# Main-Board.net
KiCad netlist of a schematic drawn in EAGLE
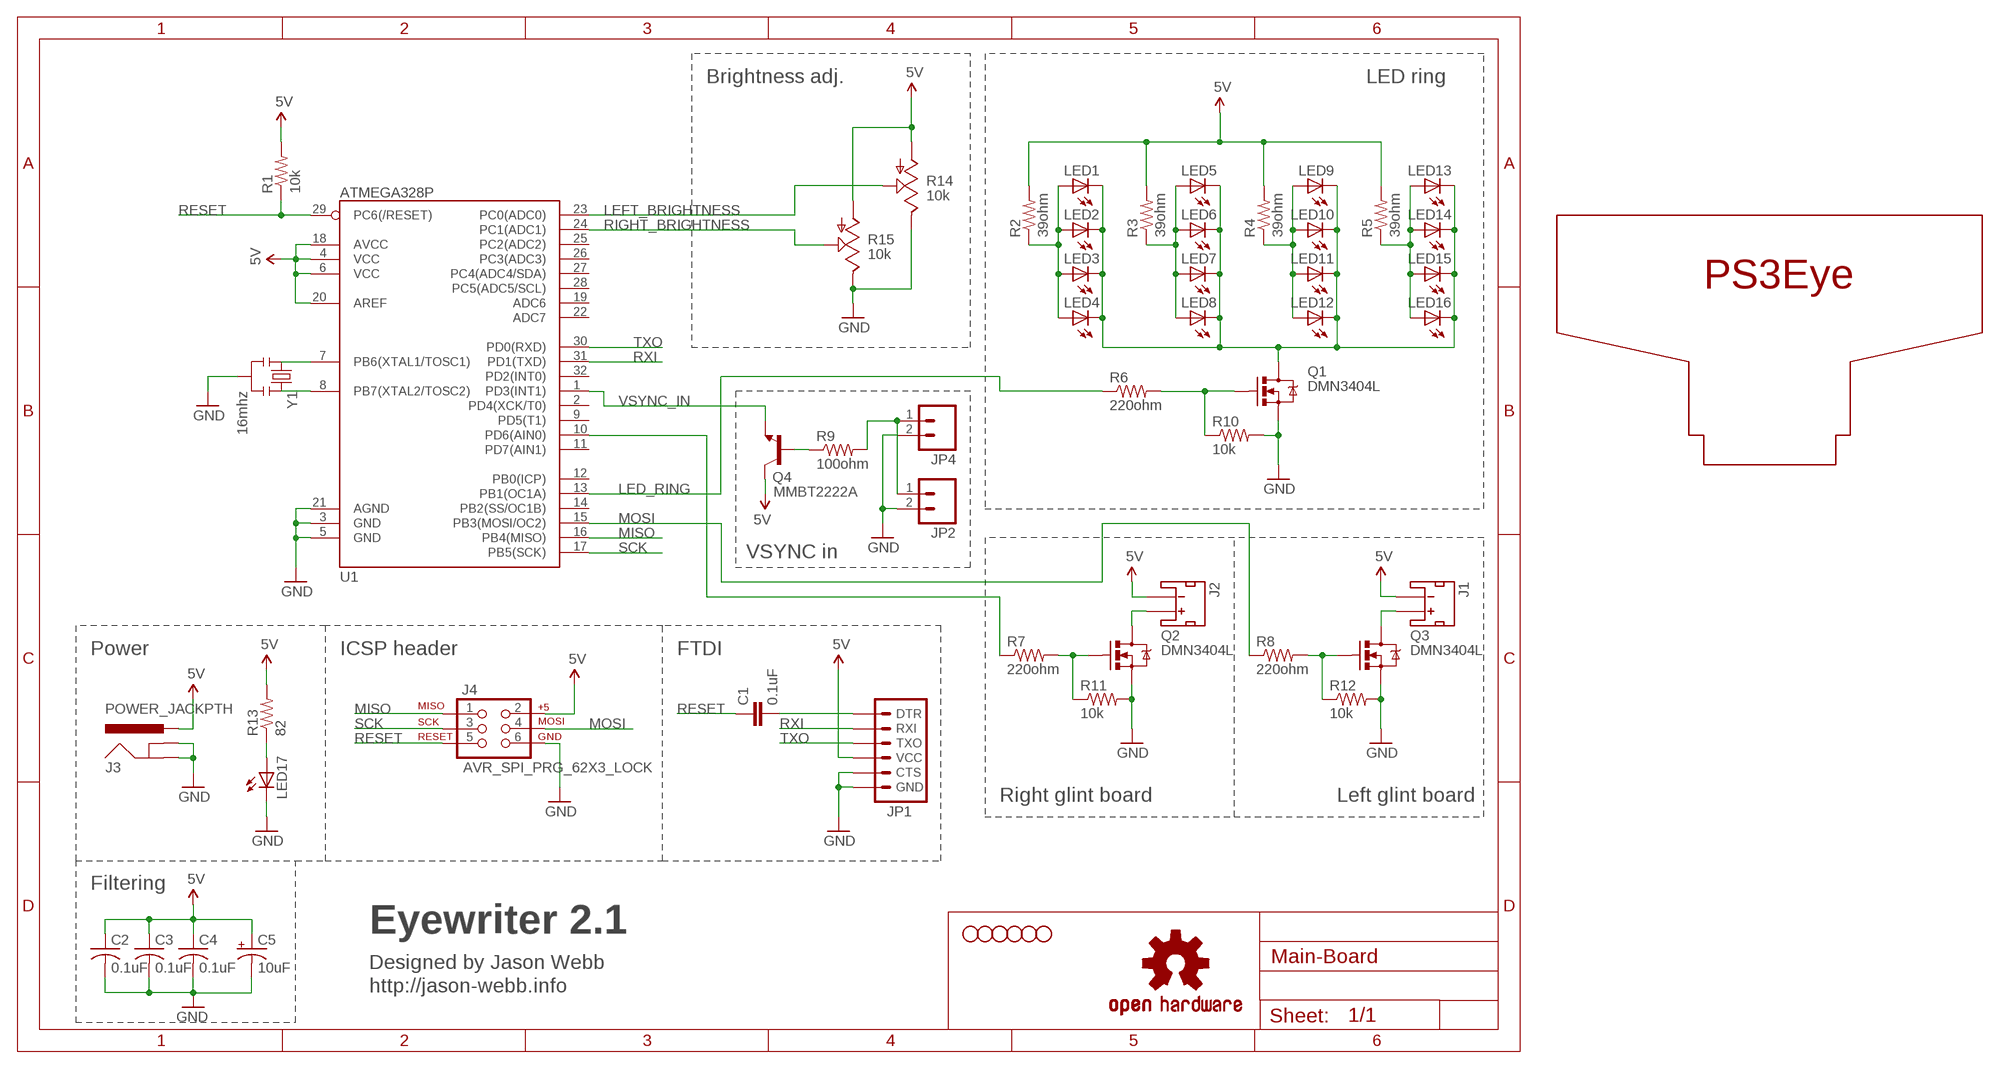
[diagram p0: schematic, sheet 1]

(export (version "E")
  (design (tool "Eeschema 10.0.6"))
  (components
    (comp (ref "C1")
      (value "0.1uF")
      (footprint "eagle-import:0805")
      (libsource (lib "eagle-import") (part "CAP0805"))
    )
    (comp (ref "C2")
      (value "0.1uF")
      (footprint "eagle-import:C0805K")
      (libsource (lib "eagle-import") (part "C-USC0805K"))
    )
    (comp (ref "C3")
      (value "0.1uF")
      (footprint "eagle-import:C0805K")
      (libsource (lib "eagle-import") (part "C-USC0805K"))
    )
    (comp (ref "C4")
      (value "0.1uF")
      (footprint "eagle-import:C0805K")
      (libsource (lib "eagle-import") (part "C-USC0805K"))
    )
    (comp (ref "C5")
      (value "10uF")
      (footprint "eagle-import:A_3216-18R")
      (libsource (lib "eagle-import") (part "CPOL-USA/3216-18R"))
    )
    (comp (ref "J1")
      (value "JST_2MM_MALE")
      (footprint "eagle-import:JST-2-SMD")
      (libsource (lib "eagle-import") (part "JST_2MM_MALE"))
    )
    (comp (ref "J2")
      (value "JST_2MM_MALE")
      (footprint "eagle-import:JST-2-SMD")
      (libsource (lib "eagle-import") (part "JST_2MM_MALE"))
    )
    (comp (ref "J3")
      (value "POWER_JACKPTH")
      (footprint "eagle-import:POWER_JACK_PTH")
      (libsource (lib "eagle-import") (part "POWER_JACKPTH"))
    )
    (comp (ref "J4")
      (value "AVR_SPI_PRG_62X3_LOCK")
      (footprint "eagle-import:2X3_LOCK")
      (libsource (lib "eagle-import") (part "AVR_SPI_PRG_62X3_LOCK"))
    )
    (comp (ref "JP1")
      (value "ARDUINO_SERIAL_PROGRAMLOCK")
      (footprint "eagle-import:1X06_LOCK")
      (libsource (lib "eagle-import") (part "ARDUINO_SERIAL_PROGRAMLOCK"))
    )
    (comp (ref "JP2")
      (value "M02PTH")
      (footprint "eagle-import:1X02")
      (libsource (lib "eagle-import") (part "M02PTH"))
    )
    (comp (ref "JP4")
      (value "M02PTH")
      (footprint "eagle-import:1X02")
      (libsource (lib "eagle-import") (part "M02PTH"))
    )
    (comp (ref "LED1")
      (value "LED5MM")
      (footprint "eagle-import:LED5MM")
      (libsource (lib "eagle-import") (part "LED5MM"))
    )
    (comp (ref "LED2")
      (value "LED5MM")
      (footprint "eagle-import:LED5MM")
      (libsource (lib "eagle-import") (part "LED5MM"))
    )
    (comp (ref "LED3")
      (value "LED5MM")
      (footprint "eagle-import:LED5MM")
      (libsource (lib "eagle-import") (part "LED5MM"))
    )
    (comp (ref "LED4")
      (value "LED5MM")
      (footprint "eagle-import:LED5MM")
      (libsource (lib "eagle-import") (part "LED5MM"))
    )
    (comp (ref "LED5")
      (value "LED5MM")
      (footprint "eagle-import:LED5MM")
      (libsource (lib "eagle-import") (part "LED5MM"))
    )
    (comp (ref "LED6")
      (value "LED5MM")
      (footprint "eagle-import:LED5MM")
      (libsource (lib "eagle-import") (part "LED5MM"))
    )
    (comp (ref "LED7")
      (value "LED5MM")
      (footprint "eagle-import:LED5MM")
      (libsource (lib "eagle-import") (part "LED5MM"))
    )
    (comp (ref "LED8")
      (value "LED5MM")
      (footprint "eagle-import:LED5MM")
      (libsource (lib "eagle-import") (part "LED5MM"))
    )
    (comp (ref "LED9")
      (value "LED5MM")
      (footprint "eagle-import:LED5MM")
      (libsource (lib "eagle-import") (part "LED5MM"))
    )
    (comp (ref "LED10")
      (value "LED5MM")
      (footprint "eagle-import:LED5MM")
      (libsource (lib "eagle-import") (part "LED5MM"))
    )
    (comp (ref "LED11")
      (value "LED5MM")
      (footprint "eagle-import:LED5MM")
      (libsource (lib "eagle-import") (part "LED5MM"))
    )
    (comp (ref "LED12")
      (value "LED5MM")
      (footprint "eagle-import:LED5MM")
      (libsource (lib "eagle-import") (part "LED5MM"))
    )
    (comp (ref "LED13")
      (value "LED5MM")
      (footprint "eagle-import:LED5MM")
      (libsource (lib "eagle-import") (part "LED5MM"))
    )
    (comp (ref "LED14")
      (value "LED5MM")
      (footprint "eagle-import:LED5MM")
      (libsource (lib "eagle-import") (part "LED5MM"))
    )
    (comp (ref "LED15")
      (value "LED5MM")
      (footprint "eagle-import:LED5MM")
      (libsource (lib "eagle-import") (part "LED5MM"))
    )
    (comp (ref "LED16")
      (value "LED5MM")
      (footprint "eagle-import:LED5MM")
      (libsource (lib "eagle-import") (part "LED5MM"))
    )
    (comp (ref "LED17")
      (value "LEDCHIPLED_0805")
      (footprint "eagle-import:CHIPLED_0805")
      (libsource (lib "eagle-import") (part "LEDCHIPLED_0805"))
    )
    (comp (ref "LOGO1")
      (value "OSHW-LOGOL")
      (footprint "eagle-import:OSHW-LOGO-L")
      (libsource (lib "eagle-import") (part "OSHW-LOGOL"))
    )
    (comp (ref "Q1")
      (value "DMN3404L")
      (footprint "eagle-import:SOT23-3")
      (libsource (lib "eagle-import") (part "MOSFET-NCHANNELSMD"))
    )
    (comp (ref "Q2")
      (value "DMN3404L")
      (footprint "eagle-import:SOT23-3")
      (libsource (lib "eagle-import") (part "MOSFET-NCHANNELSMD"))
    )
    (comp (ref "Q3")
      (value "DMN3404L")
      (footprint "eagle-import:SOT23-3")
      (libsource (lib "eagle-import") (part "MOSFET-NCHANNELSMD"))
    )
    (comp (ref "Q4")
      (value "MMBT2222A")
      (footprint "eagle-import:SOT23")
      (libsource (lib "eagle-import") (part "TRANSISTOR_NPNSOT23"))
    )
    (comp (ref "R1")
      (value "10k")
      (footprint "eagle-import:0805")
      (libsource (lib "eagle-import") (part "RESISTOR0805-RES"))
    )
    (comp (ref "R2")
      (value "39ohm")
      (footprint "eagle-import:0309_10")
      (libsource (lib "eagle-import") (part "R-US_0309/10"))
    )
    (comp (ref "R3")
      (value "39ohm")
      (footprint "eagle-import:0309_10")
      (libsource (lib "eagle-import") (part "R-US_0309/10"))
    )
    (comp (ref "R4")
      (value "39ohm")
      (footprint "eagle-import:0309_10")
      (libsource (lib "eagle-import") (part "R-US_0309/10"))
    )
    (comp (ref "R5")
      (value "39ohm")
      (footprint "eagle-import:0309_10")
      (libsource (lib "eagle-import") (part "R-US_0309/10"))
    )
    (comp (ref "R6")
      (value "220ohm")
      (footprint "eagle-import:0805")
      (libsource (lib "eagle-import") (part "RESISTOR0805-RES"))
    )
    (comp (ref "R7")
      (value "220ohm")
      (footprint "eagle-import:0805")
      (libsource (lib "eagle-import") (part "RESISTOR0805-RES"))
    )
    (comp (ref "R8")
      (value "220ohm")
      (footprint "eagle-import:0805")
      (libsource (lib "eagle-import") (part "RESISTOR0805-RES"))
    )
    (comp (ref "R9")
      (value "100ohm")
      (footprint "eagle-import:0805")
      (libsource (lib "eagle-import") (part "RESISTOR0805-RES"))
    )
    (comp (ref "R10")
      (value "10k")
      (footprint "eagle-import:0805")
      (libsource (lib "eagle-import") (part "RESISTOR0805-RES"))
    )
    (comp (ref "R11")
      (value "10k")
      (footprint "eagle-import:0805")
      (libsource (lib "eagle-import") (part "RESISTOR0805-RES"))
    )
    (comp (ref "R12")
      (value "10k")
      (footprint "eagle-import:0805")
      (libsource (lib "eagle-import") (part "RESISTOR0805-RES"))
    )
    (comp (ref "R13")
      (value "82")
      (footprint "eagle-import:0805")
      (libsource (lib "eagle-import") (part "RESISTOR0805-RES"))
    )
    (comp (ref "R14")
      (value "10k")
      (footprint "eagle-import:ALPS_POT")
      (libsource (lib "eagle-import") (part "POT"))
    )
    (comp (ref "R15")
      (value "10k")
      (footprint "eagle-import:ALPS_POT")
      (libsource (lib "eagle-import") (part "POT"))
    )
    (comp (ref "STANDOFF1")
      (value "STAND-OFF")
      (footprint "eagle-import:STAND-OFF")
      (libsource (lib "eagle-import") (part "STAND-OFF"))
    )
    (comp (ref "STANDOFF2")
      (value "STAND-OFF")
      (footprint "eagle-import:STAND-OFF")
      (libsource (lib "eagle-import") (part "STAND-OFF"))
    )
    (comp (ref "STANDOFF3")
      (value "STAND-OFF")
      (footprint "eagle-import:STAND-OFF")
      (libsource (lib "eagle-import") (part "STAND-OFF"))
    )
    (comp (ref "STANDOFF4")
      (value "STAND-OFF")
      (footprint "eagle-import:STAND-OFF")
      (libsource (lib "eagle-import") (part "STAND-OFF"))
    )
    (comp (ref "STANDOFF5")
      (value "STAND-OFF")
      (footprint "eagle-import:STAND-OFF")
      (libsource (lib "eagle-import") (part "STAND-OFF"))
    )
    (comp (ref "STANDOFF6")
      (value "STAND-OFF")
      (footprint "eagle-import:STAND-OFF")
      (libsource (lib "eagle-import") (part "STAND-OFF"))
    )
    (comp (ref "U$1")
      (value "PS3EYE")
      (footprint "eagle-import:PS3EYE")
      (libsource (lib "eagle-import") (part "PS3EYE"))
    )
    (comp (ref "U1")
      (value "ATMEGA328P")
      (footprint "eagle-import:TQFP32-08")
      (libsource (lib "eagle-import") (part "ATMEGA328_SMT"))
    )
    (comp (ref "Y1")
      (value "16mhz")
      (footprint "eagle-import:RESONATOR-SMD")
      (libsource (lib "eagle-import") (part "RESONATOR16MHZ"))
    )
  )
  (nets
    (net (code "1") (name "/LED_RING") (class "Default")
      (node (ref "R6") (pin "1") (pinfunction "1_1") (pintype "passive"))
      (node (ref "U1") (pin "13") (pinfunction "PB1(OC1A)_13") (pintype "bidirectional"))
    )
    (net (code "2") (name "/LEFT_BRIGHTNESS") (class "Default")
      (node (ref "R14") (pin "P$2") (pinfunction "S_P$2") (pintype "passive"))
      (node (ref "U1") (pin "23") (pinfunction "PC0(ADC0)_23") (pintype "bidirectional"))
    )
    (net (code "3") (name "/MISO") (class "Default")
      (node (ref "J4") (pin "1") (pinfunction "1_1") (pintype "passive"))
      (node (ref "U1") (pin "16") (pinfunction "PB4(MISO)_16") (pintype "bidirectional"))
    )
    (net (code "4") (name "/MOSI") (class "Default")
      (node (ref "J4") (pin "4") (pinfunction "4_4") (pintype "passive"))
      (node (ref "R7") (pin "1") (pinfunction "1_1") (pintype "passive"))
      (node (ref "U1") (pin "10") (pinfunction "PD6(AIN0)_10") (pintype "bidirectional"))
    )
    (net (code "5") (name "/RESET") (class "Default")
      (node (ref "C1") (pin "1") (pinfunction "1_1") (pintype "passive"))
      (node (ref "J4") (pin "5") (pinfunction "5_5") (pintype "passive"))
      (node (ref "R1") (pin "1") (pinfunction "1_1") (pintype "passive"))
      (node (ref "U1") (pin "29") (pinfunction "PC6(/RESET)_29") (pintype "bidirectional"))
    )
    (net (code "6") (name "/RIGHT_BRIGHTNESS") (class "Default")
      (node (ref "R15") (pin "P$2") (pinfunction "S_P$2") (pintype "passive"))
      (node (ref "U1") (pin "24") (pinfunction "PC1(ADC1)_24") (pintype "bidirectional"))
    )
    (net (code "7") (name "/RXI") (class "Default")
      (node (ref "JP1") (pin "2") (pinfunction "RXI_2") (pintype "passive"))
      (node (ref "U1") (pin "31") (pinfunction "PD1(TXD)_31") (pintype "bidirectional"))
    )
    (net (code "8") (name "/SCK") (class "Default")
      (node (ref "J4") (pin "3") (pinfunction "3_3") (pintype "passive"))
      (node (ref "U1") (pin "17") (pinfunction "PB5(SCK)_17") (pintype "bidirectional"))
    )
    (net (code "9") (name "/TXO") (class "Default")
      (node (ref "JP1") (pin "3") (pinfunction "TXO_3") (pintype "passive"))
      (node (ref "U1") (pin "30") (pinfunction "PD0(RXD)_30") (pintype "bidirectional"))
    )
    (net (code "10") (name "/VSYNC_IN") (class "Default")
      (node (ref "Q4") (pin "2") (pinfunction "E_2") (pintype "passive"))
      (node (ref "U1") (pin "1") (pinfunction "PD3(INT1)_1") (pintype "bidirectional"))
    )
    (net (code "11") (name "5V") (class "Default")
      (node (ref "C2") (pin "1") (pinfunction "1_1") (pintype "passive"))
      (node (ref "C3") (pin "1") (pinfunction "1_1") (pintype "passive"))
      (node (ref "C4") (pin "1") (pinfunction "1_1") (pintype "passive"))
      (node (ref "C5") (pin "+") (pinfunction "+_+") (pintype "passive"))
      (node (ref "J1") (pin "1") (pinfunction "-_1") (pintype "bidirectional"))
      (node (ref "J2") (pin "1") (pinfunction "-_1") (pintype "bidirectional"))
      (node (ref "J3") (pin "PWR") (pinfunction "PWR_PWR") (pintype "bidirectional"))
      (node (ref "J4") (pin "2") (pinfunction "2_2") (pintype "passive"))
      (node (ref "JP1") (pin "4") (pinfunction "VCC_4") (pintype "passive"))
      (node (ref "Q4") (pin "3") (pinfunction "C_3") (pintype "passive"))
      (node (ref "R1") (pin "2") (pinfunction "2_2") (pintype "passive"))
      (node (ref "R13") (pin "2") (pinfunction "2_2") (pintype "passive"))
      (node (ref "R14") (pin "P$3") (pinfunction "A_P$3") (pintype "passive"))
      (node (ref "R15") (pin "P$3") (pinfunction "A_P$3") (pintype "passive"))
      (node (ref "R2") (pin "2") (pinfunction "2_2") (pintype "passive"))
      (node (ref "R3") (pin "2") (pinfunction "2_2") (pintype "passive"))
      (node (ref "R4") (pin "2") (pinfunction "2_2") (pintype "passive"))
      (node (ref "R5") (pin "2") (pinfunction "2_2") (pintype "passive"))
      (node (ref "U1") (pin "18") (pinfunction "AVCC_18") (pintype "bidirectional"))
      (node (ref "U1") (pin "20") (pinfunction "AREF_20") (pintype "bidirectional"))
      (node (ref "U1") (pin "4") (pinfunction "VCC_4") (pintype "bidirectional"))
      (node (ref "U1") (pin "6") (pinfunction "VCC_6") (pintype "bidirectional"))
    )
    (net (code "12") (name "GND") (class "Default")
      (node (ref "C2") (pin "2") (pinfunction "2_2") (pintype "passive"))
      (node (ref "C3") (pin "2") (pinfunction "2_2") (pintype "passive"))
      (node (ref "C4") (pin "2") (pinfunction "2_2") (pintype "passive"))
      (node (ref "C5") (pin "-") (pinfunction "-_-") (pintype "passive"))
      (node (ref "J3") (pin "GND") (pinfunction "GND_GND") (pintype "bidirectional"))
      (node (ref "J3") (pin "GNDBREAK") (pinfunction "GNDBREAK_GNDBREAK") (pintype "bidirectional"))
      (node (ref "J4") (pin "6") (pinfunction "6_6") (pintype "passive"))
      (node (ref "JP1") (pin "5") (pinfunction "CTS_5") (pintype "passive"))
      (node (ref "JP1") (pin "6") (pinfunction "GND_6") (pintype "passive"))
      (node (ref "JP2") (pin "2") (pinfunction "2_2") (pintype "passive"))
      (node (ref "JP4") (pin "2") (pinfunction "2_2") (pintype "passive"))
      (node (ref "LED17") (pin "C") (pinfunction "C_C") (pintype "passive"))
      (node (ref "Q1") (pin "2") (pinfunction "S_2") (pintype "passive"))
      (node (ref "Q2") (pin "2") (pinfunction "S_2") (pintype "passive"))
      (node (ref "Q3") (pin "2") (pinfunction "S_2") (pintype "passive"))
      (node (ref "R10") (pin "2") (pinfunction "2_2") (pintype "passive"))
      (node (ref "R11") (pin "2") (pinfunction "2_2") (pintype "passive"))
      (node (ref "R12") (pin "2") (pinfunction "2_2") (pintype "passive"))
      (node (ref "R14") (pin "P$1") (pinfunction "E_P$1") (pintype "passive"))
      (node (ref "R15") (pin "P$1") (pinfunction "E_P$1") (pintype "passive"))
      (node (ref "U1") (pin "21") (pinfunction "AGND_21") (pintype "bidirectional"))
      (node (ref "U1") (pin "3") (pinfunction "GND_3") (pintype "bidirectional"))
      (node (ref "U1") (pin "5") (pinfunction "GND_5") (pintype "bidirectional"))
      (node (ref "Y1") (pin "2") (pinfunction "2_2") (pintype "passive"))
    )
    (net (code "13") (name "Net-(J1-+)") (class "Default")
      (node (ref "J1") (pin "2") (pinfunction "+_2") (pintype "bidirectional"))
      (node (ref "Q3") (pin "3") (pinfunction "D_3") (pintype "passive"))
    )
    (net (code "14") (name "Net-(J2-+)") (class "Default")
      (node (ref "J2") (pin "2") (pinfunction "+_2") (pintype "bidirectional"))
      (node (ref "Q2") (pin "3") (pinfunction "D_3") (pintype "passive"))
    )
    (net (code "15") (name "Net-(JP1-DTR)") (class "Default")
      (node (ref "C1") (pin "2") (pinfunction "2_2") (pintype "passive"))
      (node (ref "JP1") (pin "1") (pinfunction "DTR_1") (pintype "passive"))
    )
    (net (code "16") (name "Net-(JP2-Pad1)") (class "Default")
      (node (ref "JP2") (pin "1") (pinfunction "1_1") (pintype "passive"))
      (node (ref "JP4") (pin "1") (pinfunction "1_1") (pintype "passive"))
      (node (ref "R9") (pin "2") (pinfunction "2_2") (pintype "passive"))
    )
    (net (code "17") (name "Net-(LED1-C)") (class "Default")
      (node (ref "LED1") (pin "K") (pinfunction "C_K") (pintype "passive"))
      (node (ref "LED10") (pin "K") (pinfunction "C_K") (pintype "passive"))
      (node (ref "LED11") (pin "K") (pinfunction "C_K") (pintype "passive"))
      (node (ref "LED12") (pin "K") (pinfunction "C_K") (pintype "passive"))
      (node (ref "LED13") (pin "K") (pinfunction "C_K") (pintype "passive"))
      (node (ref "LED14") (pin "K") (pinfunction "C_K") (pintype "passive"))
      (node (ref "LED15") (pin "K") (pinfunction "C_K") (pintype "passive"))
      (node (ref "LED16") (pin "K") (pinfunction "C_K") (pintype "passive"))
      (node (ref "LED2") (pin "K") (pinfunction "C_K") (pintype "passive"))
      (node (ref "LED3") (pin "K") (pinfunction "C_K") (pintype "passive"))
      (node (ref "LED4") (pin "K") (pinfunction "C_K") (pintype "passive"))
      (node (ref "LED5") (pin "K") (pinfunction "C_K") (pintype "passive"))
      (node (ref "LED6") (pin "K") (pinfunction "C_K") (pintype "passive"))
      (node (ref "LED7") (pin "K") (pinfunction "C_K") (pintype "passive"))
      (node (ref "LED8") (pin "K") (pinfunction "C_K") (pintype "passive"))
      (node (ref "LED9") (pin "K") (pinfunction "C_K") (pintype "passive"))
      (node (ref "Q1") (pin "3") (pinfunction "D_3") (pintype "passive"))
    )
    (net (code "18") (name "Net-(LED1-PadA)") (class "Default")
      (node (ref "LED1") (pin "A") (pinfunction "A_A") (pintype "passive"))
      (node (ref "LED2") (pin "A") (pinfunction "A_A") (pintype "passive"))
      (node (ref "LED3") (pin "A") (pinfunction "A_A") (pintype "passive"))
      (node (ref "LED4") (pin "A") (pinfunction "A_A") (pintype "passive"))
      (node (ref "R2") (pin "1") (pinfunction "1_1") (pintype "passive"))
    )
    (net (code "19") (name "Net-(LED5-PadA)") (class "Default")
      (node (ref "LED5") (pin "A") (pinfunction "A_A") (pintype "passive"))
      (node (ref "LED6") (pin "A") (pinfunction "A_A") (pintype "passive"))
      (node (ref "LED7") (pin "A") (pinfunction "A_A") (pintype "passive"))
      (node (ref "LED8") (pin "A") (pinfunction "A_A") (pintype "passive"))
      (node (ref "R3") (pin "1") (pinfunction "1_1") (pintype "passive"))
    )
    (net (code "20") (name "Net-(LED10-PadA)") (class "Default")
      (node (ref "LED10") (pin "A") (pinfunction "A_A") (pintype "passive"))
      (node (ref "LED11") (pin "A") (pinfunction "A_A") (pintype "passive"))
      (node (ref "LED12") (pin "A") (pinfunction "A_A") (pintype "passive"))
      (node (ref "LED9") (pin "A") (pinfunction "A_A") (pintype "passive"))
      (node (ref "R4") (pin "1") (pinfunction "1_1") (pintype "passive"))
    )
    (net (code "21") (name "Net-(LED13-PadA)") (class "Default")
      (node (ref "LED13") (pin "A") (pinfunction "A_A") (pintype "passive"))
      (node (ref "LED14") (pin "A") (pinfunction "A_A") (pintype "passive"))
      (node (ref "LED15") (pin "A") (pinfunction "A_A") (pintype "passive"))
      (node (ref "LED16") (pin "A") (pinfunction "A_A") (pintype "passive"))
      (node (ref "R5") (pin "1") (pinfunction "1_1") (pintype "passive"))
    )
    (net (code "22") (name "Net-(LED17-PadA)") (class "Default")
      (node (ref "LED17") (pin "A") (pinfunction "A_A") (pintype "passive"))
      (node (ref "R13") (pin "1") (pinfunction "1_1") (pintype "passive"))
    )
    (net (code "23") (name "Net-(Q1-G)") (class "Default")
      (node (ref "Q1") (pin "1") (pinfunction "G_1") (pintype "passive"))
      (node (ref "R10") (pin "1") (pinfunction "1_1") (pintype "passive"))
      (node (ref "R6") (pin "2") (pinfunction "2_2") (pintype "passive"))
    )
    (net (code "24") (name "Net-(Q2-G)") (class "Default")
      (node (ref "Q2") (pin "1") (pinfunction "G_1") (pintype "passive"))
      (node (ref "R11") (pin "1") (pinfunction "1_1") (pintype "passive"))
      (node (ref "R7") (pin "2") (pinfunction "2_2") (pintype "passive"))
    )
    (net (code "25") (name "Net-(Q3-G)") (class "Default")
      (node (ref "Q3") (pin "1") (pinfunction "G_1") (pintype "passive"))
      (node (ref "R12") (pin "1") (pinfunction "1_1") (pintype "passive"))
      (node (ref "R8") (pin "2") (pinfunction "2_2") (pintype "passive"))
    )
    (net (code "26") (name "Net-(Q4-B)") (class "Default")
      (node (ref "Q4") (pin "1") (pinfunction "B_1") (pintype "passive"))
      (node (ref "R9") (pin "1") (pinfunction "1_1") (pintype "passive"))
    )
    (net (code "27") (name "Net-(U1-PB3(MOSI{slash}OC2))") (class "Default")
      (node (ref "R8") (pin "1") (pinfunction "1_1") (pintype "passive"))
      (node (ref "U1") (pin "15") (pinfunction "PB3(MOSI/OC2)_15") (pintype "bidirectional"))
    )
    (net (code "28") (name "Net-(U1-PB6(XTAL1{slash}TOSC1))") (class "Default")
      (node (ref "U1") (pin "7") (pinfunction "PB6(XTAL1/TOSC1)_7") (pintype "bidirectional"))
      (node (ref "Y1") (pin "1") (pinfunction "1_1") (pintype "passive"))
    )
    (net (code "29") (name "Net-(U1-PB7(XTAL2{slash}TOSC2))") (class "Default")
      (node (ref "U1") (pin "8") (pinfunction "PB7(XTAL2/TOSC2)_8") (pintype "bidirectional"))
      (node (ref "Y1") (pin "3") (pinfunction "3_3") (pintype "passive"))
    )
    (net (code "30") (name "unconnected-(J1-PAD1-PadNC1)") (class "Default")
      (node (ref "J1") (pin "NC1") (pinfunction "PAD1_NC1") (pintype "bidirectional"))
    )
    (net (code "31") (name "unconnected-(J1-PAD2-PadNC2)") (class "Default")
      (node (ref "J1") (pin "NC2") (pinfunction "PAD2_NC2") (pintype "bidirectional"))
    )
    (net (code "32") (name "unconnected-(J2-PAD1-PadNC1)") (class "Default")
      (node (ref "J2") (pin "NC1") (pinfunction "PAD1_NC1") (pintype "bidirectional"))
    )
    (net (code "33") (name "unconnected-(J2-PAD2-PadNC2)") (class "Default")
      (node (ref "J2") (pin "NC2") (pinfunction "PAD2_NC2") (pintype "bidirectional"))
    )
    (net (code "34") (name "unconnected-(U1-ADC6-Pad19)") (class "Default")
      (node (ref "U1") (pin "19") (pinfunction "ADC6_19") (pintype "bidirectional"))
    )
    (net (code "35") (name "unconnected-(U1-ADC7-Pad22)") (class "Default")
      (node (ref "U1") (pin "22") (pinfunction "ADC7_22") (pintype "bidirectional"))
    )
    (net (code "36") (name "unconnected-(U1-PB0(ICP)-Pad12)") (class "Default")
      (node (ref "U1") (pin "12") (pinfunction "PB0(ICP)_12") (pintype "bidirectional"))
    )
    (net (code "37") (name "unconnected-(U1-PB2(SS{slash}OC1B)-Pad14)") (class "Default")
      (node (ref "U1") (pin "14") (pinfunction "PB2(SS/OC1B)_14") (pintype "bidirectional"))
    )
    (net (code "38") (name "unconnected-(U1-PC2(ADC2)-Pad25)") (class "Default")
      (node (ref "U1") (pin "25") (pinfunction "PC2(ADC2)_25") (pintype "bidirectional"))
    )
    (net (code "39") (name "unconnected-(U1-PC3(ADC3)-Pad26)") (class "Default")
      (node (ref "U1") (pin "26") (pinfunction "PC3(ADC3)_26") (pintype "bidirectional"))
    )
    (net (code "40") (name "unconnected-(U1-PC4(ADC4{slash}SDA)-Pad27)") (class "Default")
      (node (ref "U1") (pin "27") (pinfunction "PC4(ADC4/SDA)_27") (pintype "bidirectional"))
    )
    (net (code "41") (name "unconnected-(U1-PC5(ADC5{slash}SCL)-Pad28)") (class "Default")
      (node (ref "U1") (pin "28") (pinfunction "PC5(ADC5/SCL)_28") (pintype "bidirectional"))
    )
    (net (code "42") (name "unconnected-(U1-PD2(INT0)-Pad32)") (class "Default")
      (node (ref "U1") (pin "32") (pinfunction "PD2(INT0)_32") (pintype "bidirectional"))
    )
    (net (code "43") (name "unconnected-(U1-PD4(XCK{slash}T0)-Pad2)") (class "Default")
      (node (ref "U1") (pin "2") (pinfunction "PD4(XCK/T0)_2") (pintype "bidirectional"))
    )
    (net (code "44") (name "unconnected-(U1-PD5(T1)-Pad9)") (class "Default")
      (node (ref "U1") (pin "9") (pinfunction "PD5(T1)_9") (pintype "bidirectional"))
    )
    (net (code "45") (name "unconnected-(U1-PD7(AIN1)-Pad11)") (class "Default")
      (node (ref "U1") (pin "11") (pinfunction "PD7(AIN1)_11") (pintype "bidirectional"))
    )
  )
)
